# LED_low_side_control.net
KiCad netlist of a schematic drawn in Altium Designer
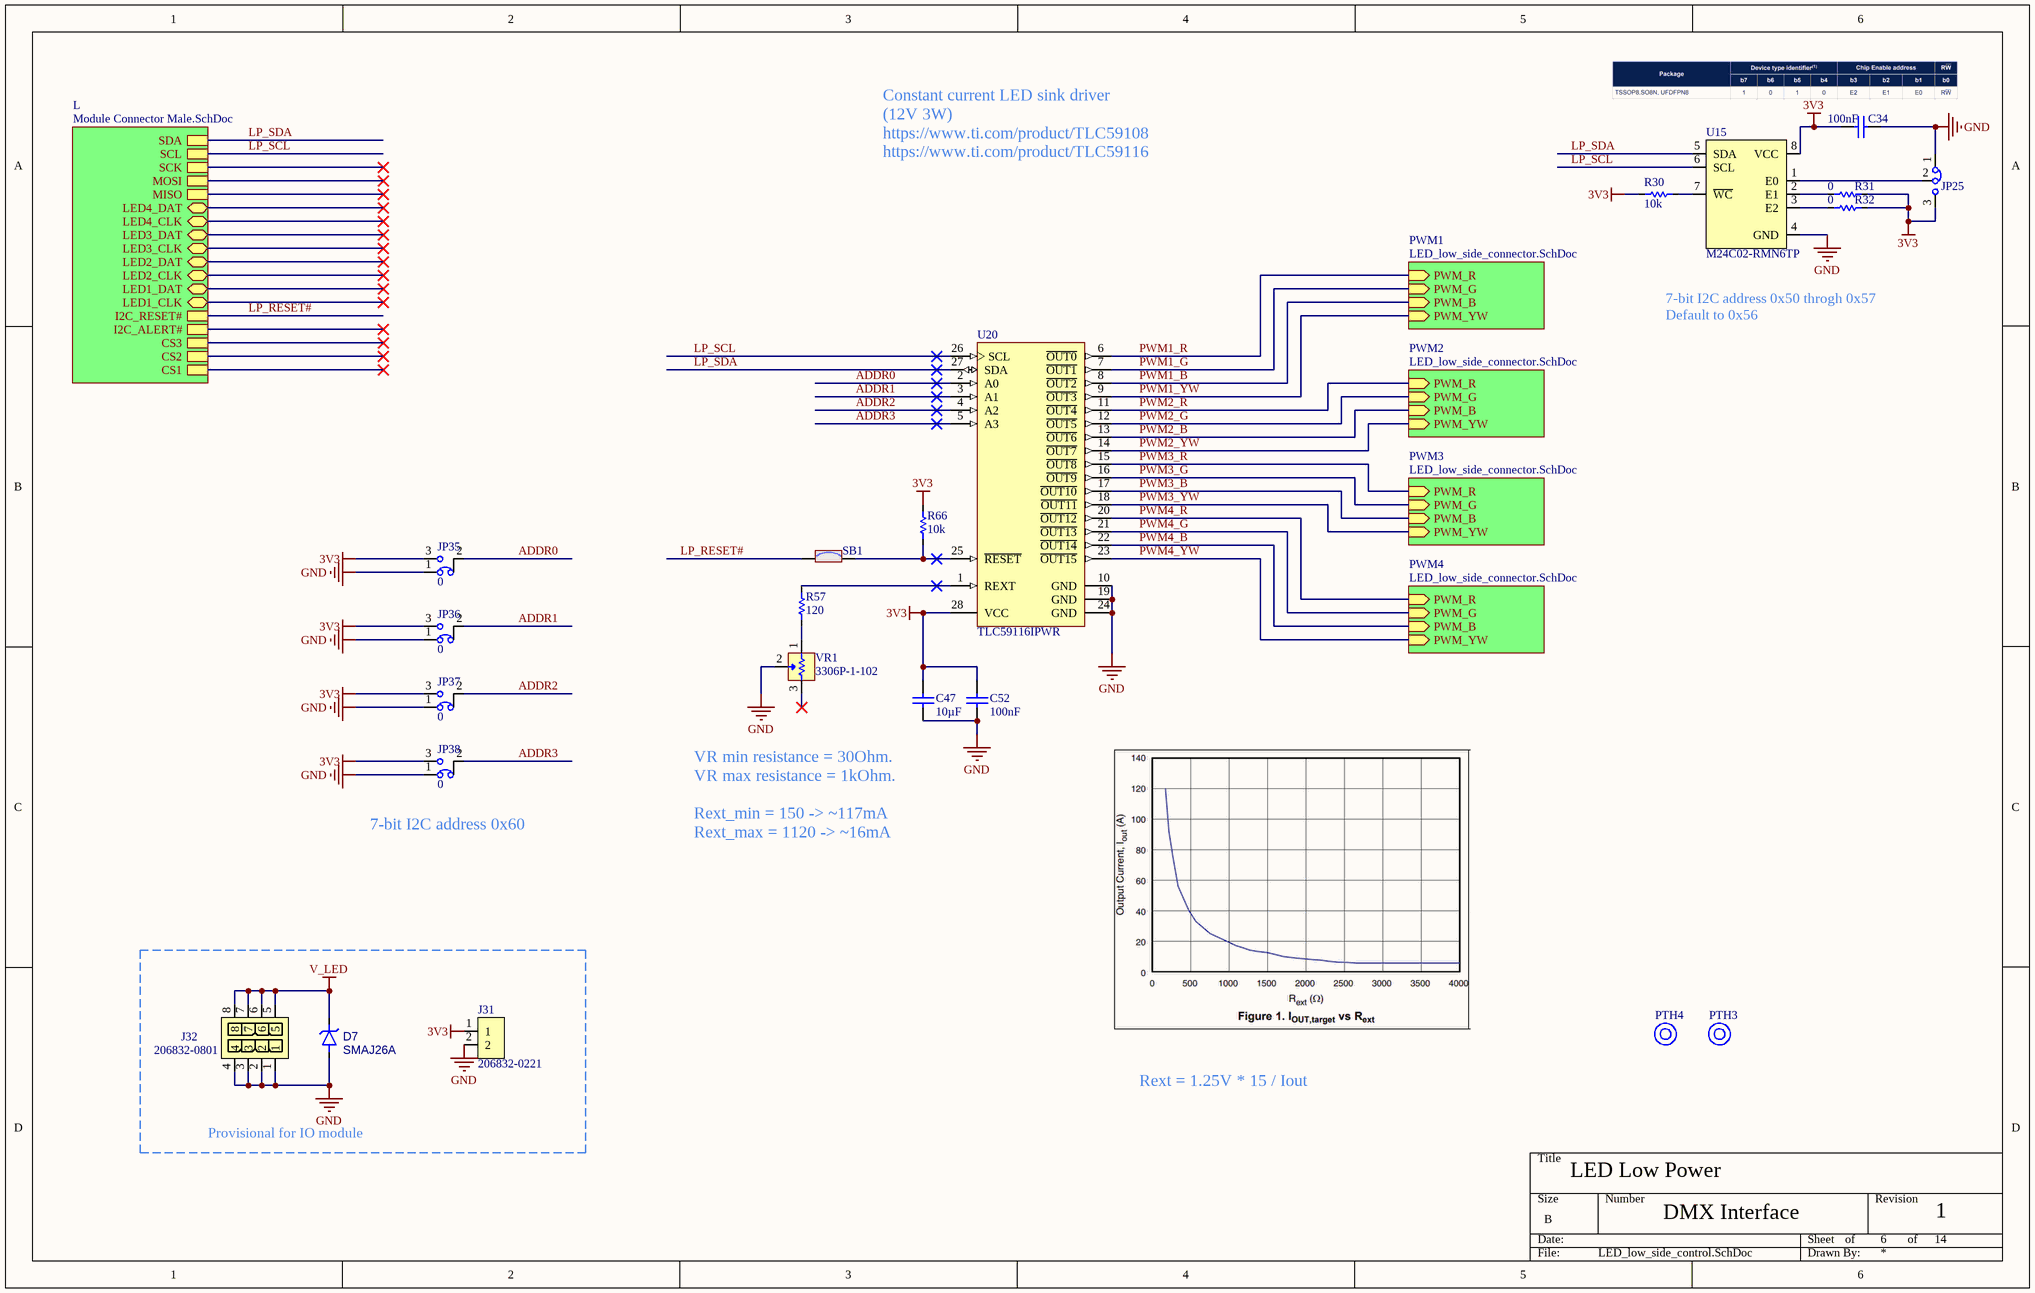
[diagram p0: LED_low_side_control.SchDoc]

(export (version "E")
  (design (tool "Eeschema 10.0.6"))
  (components
    (comp (ref "C34")
      (value "100nF")
      (footprint "CAPC1608X10N_0603_MED")
      (fields (field (name "Comment") "CC0603KRX7R0BB104"))
      (libsource (lib "Equus Computer Systems") (part "CAP-NP-2"))
    )
    (comp (ref "C47")
      (value "10µF")
      (footprint "CAPC2012X14N_0805_MED")
      (description "Ceramic Capacitor, Multilayer, Ceramic, 10uF, 16V, 10%, X6S, 0805")
      (fields (field (name "TOLERANCE") "10%") (field (name "Comment") "GRM21BC81C106KA73L"))
      (libsource (lib "Equus Computer Systems") (part "CAP-NP-2"))
    )
    (comp (ref "C52")
      (value "100nF")
      (footprint "CAPC1608X10N_0603_MED")
      (fields (field (name "Comment") "CC0603KRX7R0BB104"))
      (libsource (lib "Equus Computer Systems") (part "CAP-NP-2"))
    )
    (comp (ref "D7")
      (value "SMAJ26A")
      (footprint "FP-SMAJ-MFG")
      (description "Trans Voltage Suppressor Diode, 400W, 26V V(RWM), Unidirectional, 1 Element, Silicon, DO-214AC")
      (libsource (lib "Equus Computer Systems") (part "DIODE-TVS-2"))
    )
    (comp (ref "J31")
      (value "206832-0221")
      (footprint "206832-0221-Footprint-1")
      (description "Micro-Fit+, Vertial Header, 2 Position 3mm pitch")
      (libsource (lib "Equus Computer Systems") (part "HEADER-2x1"))
    )
    (comp (ref "J32")
      (value "206832-0801")
      (footprint "206832-0801-Footprint-1")
      (description "Micro-Fit+, Vertical Header, 8 pin")
      (libsource (lib "Equus Computer Systems") (part "206832-0801-Symbol-1"))
    )
    (comp (ref "JP25")
      (value "Jumper 3 x 1 Bridge 1-2 Solder Bridge")
      (footprint "Jumper 3 Solder Bridge 1-2 0603")
      (description "0603 Solder Bridge Jumper Surface Mount")
      (fields (field (name "TOLERANCE") "1%"))
      (libsource (lib "Equus Computer Systems") (part "Jumper 3 Bridge 12"))
    )
    (comp (ref "JP35")
      (value "0")
      (footprint "Jumper 3 Solder Bridge 1-2 0603")
      (description "0603 Solder Bridge Jumper Surface Mount")
      (fields
        (field (name "TOLERANCE") "1%")
        (field (name "Comment") "Jumper 3 x 1 Bridge 1-2 Solder Bridge")
      )
      (libsource (lib "") (part "Jumper 3 Bridge 12_1"))
    )
    (comp (ref "JP36")
      (value "0")
      (footprint "Jumper 3 Solder Bridge 1-2 0603")
      (description "0603 Solder Bridge Jumper Surface Mount")
      (fields
        (field (name "TOLERANCE") "1%")
        (field (name "Comment") "Jumper 3 x 1 Bridge 1-2 Solder Bridge")
      )
      (libsource (lib "") (part "Jumper 3 Bridge 12_1"))
    )
    (comp (ref "JP37")
      (value "0")
      (footprint "Jumper 3 Solder Bridge 1-2 0603")
      (description "0603 Solder Bridge Jumper Surface Mount")
      (fields
        (field (name "TOLERANCE") "1%")
        (field (name "Comment") "Jumper 3 x 1 Bridge 1-2 Solder Bridge")
      )
      (libsource (lib "") (part "Jumper 3 Bridge 12_1"))
    )
    (comp (ref "JP38")
      (value "0")
      (footprint "Jumper 3 Solder Bridge 1-2 0603")
      (description "0603 Solder Bridge Jumper Surface Mount")
      (fields
        (field (name "TOLERANCE") "1%")
        (field (name "Comment") "Jumper 3 x 1 Bridge 1-2 Solder Bridge")
      )
      (libsource (lib "") (part "Jumper 3 Bridge 12_1"))
    )
    (comp (ref "PTH3")
      (value "Mounting Hole NPTH")
      (footprint "Mounting Hole M3 No Washer NPTH")
      (libsource (lib "Equus Computer Systems") (part "Mounting Hole NPTH"))
    )
    (comp (ref "PTH4")
      (value "Mounting Hole NPTH")
      (footprint "Mounting Hole M3 No Washer NPTH")
      (libsource (lib "Equus Computer Systems") (part "Mounting Hole NPTH"))
    )
    (comp (ref "R30")
      (value "10k")
      (footprint "RESC1608X06N_0603_MED")
      (fields
        (field (name "TOLERANCE") "1%")
        (field (name "POWER") "100mW")
        (field (name "Comment") "RC0603FR-1010KL")
      )
      (libsource (lib "Equus Computer Systems") (part "RES-2"))
    )
    (comp (ref "R31")
      (value "0")
      (footprint "RESC1608X06N_0603_MED")
      (description "RC Series 0603 0.1 W 0 Ohm Jumper Surface Mount Thick Film Chip Resistor")
      (fields (field (name "POWER") "100mW") (field (name "TOLERANCE") "1%"))
      (libsource (lib "Equus Computer Systems") (part "RES-2"))
    )
    (comp (ref "R32")
      (value "0")
      (footprint "RESC1608X06N_0603_MED")
      (description "RC Series 0603 0.1 W 0 Ohm Jumper Surface Mount Thick Film Chip Resistor")
      (fields (field (name "POWER") "100mW") (field (name "TOLERANCE") "1%"))
      (libsource (lib "Equus Computer Systems") (part "RES-2"))
    )
    (comp (ref "R57")
      (value "120")
      (footprint "RESC1608X06N_0603_MED")
      (description "Res General Purpose Thick Film 0603 120 Ohm 1% 1/10W ±100ppm/°C Molded SMD Paper T/R")
      (fields (field (name "TOLERANCE") "1%") (field (name "POWER") "100mW"))
      (libsource (lib "Equus Computer Systems") (part "RES-2"))
    )
    (comp (ref "R66")
      (value "10k")
      (footprint "RESC1608X06N_0603_MED")
      (fields
        (field (name "TOLERANCE") "1%")
        (field (name "POWER") "100mW")
        (field (name "Comment") "RC0603FR-1010KL")
      )
      (libsource (lib "Equus Computer Systems") (part "RES-2"))
    )
    (comp (ref "SB1")
      (value "SolderBridge0603_On")
      (footprint "SOLDER-BRIDGE_R0603-0R")
      (description "Solder Bridge ON")
      (fields
        (field (name "INTERNAL_PART_NUMBER") "MCD-00071")
        (field (name "MANUFACTURER") "YAGEO")
        (field (name "PROVIDED_BY") "SUBCO")
      )
      (libsource (lib "Equus Computer Systems") (part "SolderBridge0603_On"))
    )
    (comp (ref "U15")
      (value "M24C02-RMN6TP")
      (footprint "M24C02-RMN6TP-SO8N-IPC_B")
      (description "M24C02 Series 2 Kb (256 x 8) 1.8 V SMT Serial I²C Bus EEPROM - SOIC-8")
      (libsource (lib "Equus Computer Systems") (part "M24C02-RMN6TP"))
    )
    (comp (ref "U20")
      (value "TLC59116IPWR")
      (footprint "PW0028A_L")
      (description "LED Driver, 16-Segment, PDSO28")
      (libsource (lib "Equus Computer Systems") (part "TI-TLC59116PW28"))
    )
    (comp (ref "VR1")
      (value "3306P-1-102")
      (footprint "3306P-1-102-Footprint-1")
      (description "Trimmer, Cermet, 0.2W, 1000ohm, 100V, 25% +/-Tol, 250ppm/Cel, 1 Turn(s)")
      (libsource (lib "Equus Computer Systems") (part "3306P-1-102-Symbol-1"))
    )
  )
  (nets
    (net (code "1") (name "/ADDR0") (class "Default")
      (node (ref "JP35") (pin "2") (pinfunction "2_2") (pintype "passive"))
      (node (ref "U20") (pin "2") (pinfunction "A0_2") (pintype "input"))
    )
    (net (code "2") (name "/ADDR1") (class "Default")
      (node (ref "JP36") (pin "2") (pinfunction "2_2") (pintype "passive"))
      (node (ref "U20") (pin "3") (pinfunction "A1_3") (pintype "input"))
    )
    (net (code "3") (name "/ADDR2") (class "Default")
      (node (ref "JP37") (pin "2") (pinfunction "2_2") (pintype "passive"))
      (node (ref "U20") (pin "4") (pinfunction "A2_4") (pintype "input"))
    )
    (net (code "4") (name "/ADDR3") (class "Default")
      (node (ref "JP38") (pin "2") (pinfunction "2_2") (pintype "passive"))
      (node (ref "U20") (pin "5") (pinfunction "A3_5") (pintype "input"))
    )
    (net (code "17") (name "/LP_RESET#") (class "Default")
      (node (ref "SB1") (pin "1") (pinfunction "1_1") (pintype "passive"))
    )
    (net (code "18") (name "/LP_SCL") (class "Default")
      (node (ref "U15") (pin "6") (pinfunction "SCL_6") (pintype "passive"))
      (node (ref "U20") (pin "26") (pinfunction "SCL_26") (pintype "input"))
    )
    (net (code "19") (name "/LP_SDA") (class "Default")
      (node (ref "U15") (pin "5") (pinfunction "SDA_5") (pintype "passive"))
      (node (ref "U20") (pin "27") (pinfunction "SDA_27") (pintype "bidirectional"))
    )
    (net (code "22") (name "/PWM1_B") (class "Default")
      (node (ref "U20") (pin "8") (pinfunction "~{OUT2}_8") (pintype "output"))
    )
    (net (code "23") (name "/PWM1_G") (class "Default")
      (node (ref "U20") (pin "7") (pinfunction "~{OUT1}_7") (pintype "output"))
    )
    (net (code "24") (name "/PWM1_R") (class "Default")
      (node (ref "U20") (pin "6") (pinfunction "~{OUT0}_6") (pintype "output"))
    )
    (net (code "25") (name "/PWM1_YW") (class "Default")
      (node (ref "U20") (pin "9") (pinfunction "~{OUT3}_9") (pintype "output"))
    )
    (net (code "26") (name "/PWM2_B") (class "Default")
      (node (ref "U20") (pin "13") (pinfunction "~{OUT6}_13") (pintype "output"))
    )
    (net (code "27") (name "/PWM2_G") (class "Default")
      (node (ref "U20") (pin "12") (pinfunction "~{OUT5}_12") (pintype "output"))
    )
    (net (code "28") (name "/PWM2_R") (class "Default")
      (node (ref "U20") (pin "11") (pinfunction "~{OUT4}_11") (pintype "output"))
    )
    (net (code "29") (name "/PWM2_YW") (class "Default")
      (node (ref "U20") (pin "14") (pinfunction "~{OUT7}_14") (pintype "output"))
    )
    (net (code "30") (name "/PWM3_B") (class "Default")
      (node (ref "U20") (pin "17") (pinfunction "~{OUT10}_17") (pintype "output"))
    )
    (net (code "31") (name "/PWM3_G") (class "Default")
      (node (ref "U20") (pin "16") (pinfunction "~{OUT9}_16") (pintype "output"))
    )
    (net (code "32") (name "/PWM3_R") (class "Default")
      (node (ref "U20") (pin "15") (pinfunction "~{OUT8}_15") (pintype "output"))
    )
    (net (code "33") (name "/PWM3_YW") (class "Default")
      (node (ref "U20") (pin "18") (pinfunction "~{OUT11}_18") (pintype "output"))
    )
    (net (code "34") (name "/PWM4_B") (class "Default")
      (node (ref "U20") (pin "22") (pinfunction "~{OUT14}_22") (pintype "output"))
    )
    (net (code "35") (name "/PWM4_G") (class "Default")
      (node (ref "U20") (pin "21") (pinfunction "~{OUT13}_21") (pintype "output"))
    )
    (net (code "36") (name "/PWM4_R") (class "Default")
      (node (ref "U20") (pin "20") (pinfunction "~{OUT12}_20") (pintype "output"))
    )
    (net (code "37") (name "/PWM4_YW") (class "Default")
      (node (ref "U20") (pin "23") (pinfunction "~{OUT15}_23") (pintype "output"))
    )
    (net (code "39") (name "3V3") (class "Default")
      (node (ref "C34") (pin "1") (pinfunction "1_1") (pintype "passive"))
      (node (ref "C47") (pin "2") (pinfunction "2_2") (pintype "passive"))
      (node (ref "C52") (pin "1") (pinfunction "1_1") (pintype "passive"))
      (node (ref "J31") (pin "1") (pinfunction "1_1") (pintype "passive"))
      (node (ref "JP25") (pin "3") (pinfunction "3_3") (pintype "passive"))
      (node (ref "JP35") (pin "3") (pinfunction "3_3") (pintype "passive"))
      (node (ref "JP36") (pin "3") (pinfunction "3_3") (pintype "passive"))
      (node (ref "JP37") (pin "3") (pinfunction "3_3") (pintype "passive"))
      (node (ref "JP38") (pin "3") (pinfunction "3_3") (pintype "passive"))
      (node (ref "R30") (pin "2") (pinfunction "2_2") (pintype "passive"))
      (node (ref "R31") (pin "1") (pinfunction "1_1") (pintype "passive"))
      (node (ref "R32") (pin "1") (pinfunction "1_1") (pintype "passive"))
      (node (ref "R66") (pin "2") (pinfunction "2_2") (pintype "passive"))
      (node (ref "U15") (pin "8") (pinfunction "VCC_8") (pintype "power_in"))
      (node (ref "U20") (pin "28") (pinfunction "VCC_28") (pintype "power_in"))
    )
    (net (code "40") (name "GND") (class "Default")
      (node (ref "C34") (pin "2") (pinfunction "2_2") (pintype "passive"))
      (node (ref "C47") (pin "1") (pinfunction "1_1") (pintype "passive"))
      (node (ref "C52") (pin "2") (pinfunction "2_2") (pintype "passive"))
      (node (ref "D7") (pin "2") (pinfunction "A_2") (pintype "passive"))
      (node (ref "J31") (pin "2") (pinfunction "2_2") (pintype "passive"))
      (node (ref "J32") (pin "1") (pinfunction "1_1") (pintype "passive"))
      (node (ref "J32") (pin "2") (pinfunction "2_2") (pintype "passive"))
      (node (ref "J32") (pin "3") (pinfunction "3_3") (pintype "passive"))
      (node (ref "J32") (pin "4") (pinfunction "4_4") (pintype "passive"))
      (node (ref "JP25") (pin "1") (pinfunction "1_1") (pintype "passive"))
      (node (ref "JP35") (pin "1") (pinfunction "1_1") (pintype "passive"))
      (node (ref "JP36") (pin "1") (pinfunction "1_1") (pintype "passive"))
      (node (ref "JP37") (pin "1") (pinfunction "1_1") (pintype "passive"))
      (node (ref "JP38") (pin "1") (pinfunction "1_1") (pintype "passive"))
      (node (ref "U15") (pin "4") (pinfunction "GND_4") (pintype "power_in"))
      (node (ref "U20") (pin "10") (pinfunction "GND_10") (pintype "power_in"))
      (node (ref "U20") (pin "19") (pinfunction "GND_19") (pintype "power_in"))
      (node (ref "U20") (pin "24") (pinfunction "GND_24") (pintype "power_in"))
      (node (ref "VR1") (pin "2") (pinfunction "Wipe_2") (pintype "passive"))
    )
    (net (code "41") (name "Net-(R57-Pad1)") (class "Default")
      (node (ref "R57") (pin "1") (pinfunction "1_1") (pintype "passive"))
      (node (ref "VR1") (pin "1") (pintype "passive"))
    )
    (net (code "42") (name "Net-(U15-E0)") (class "Default")
      (node (ref "JP25") (pin "2") (pinfunction "2_2") (pintype "passive"))
      (node (ref "U15") (pin "1") (pinfunction "E0_1") (pintype "passive"))
    )
    (net (code "43") (name "Net-(U15-E1)") (class "Default")
      (node (ref "R31") (pin "2") (pinfunction "2_2") (pintype "passive"))
      (node (ref "U15") (pin "2") (pinfunction "E1_2") (pintype "passive"))
    )
    (net (code "44") (name "Net-(U15-E2)") (class "Default")
      (node (ref "R32") (pin "2") (pinfunction "2_2") (pintype "passive"))
      (node (ref "U15") (pin "3") (pinfunction "E2_3") (pintype "passive"))
    )
    (net (code "45") (name "Net-(U15-~{WC})") (class "Default")
      (node (ref "R30") (pin "1") (pinfunction "1_1") (pintype "passive"))
      (node (ref "U15") (pin "7") (pinfunction "~{WC}_7") (pintype "passive"))
    )
    (net (code "46") (name "Net-(U20-REXT)") (class "Default")
      (node (ref "R57") (pin "2") (pinfunction "2_2") (pintype "passive"))
      (node (ref "U20") (pin "1") (pinfunction "REXT_1") (pintype "input"))
    )
    (net (code "47") (name "Net-(U20-~{RESET})") (class "Default")
      (node (ref "R66") (pin "1") (pinfunction "1_1") (pintype "passive"))
      (node (ref "SB1") (pin "2") (pinfunction "2_2") (pintype "passive"))
      (node (ref "U20") (pin "25") (pinfunction "~{RESET}_25") (pintype "input"))
    )
    (net (code "48") (name "V_LED") (class "Default")
      (node (ref "D7") (pin "1") (pinfunction "K_1") (pintype "passive"))
      (node (ref "J32") (pin "5") (pinfunction "5_5") (pintype "passive"))
      (node (ref "J32") (pin "6") (pinfunction "6_6") (pintype "passive"))
      (node (ref "J32") (pin "7") (pinfunction "7_7") (pintype "passive"))
      (node (ref "J32") (pin "8") (pinfunction "8_8") (pintype "passive"))
    )
    (net (code "49") (name "unconnected-(VR1-Pad3)") (class "Default")
      (node (ref "VR1") (pin "3") (pintype "passive+no_connect"))
    )
  )
)
